# Processor.net
KiCad netlist of a schematic drawn in Altium Designer
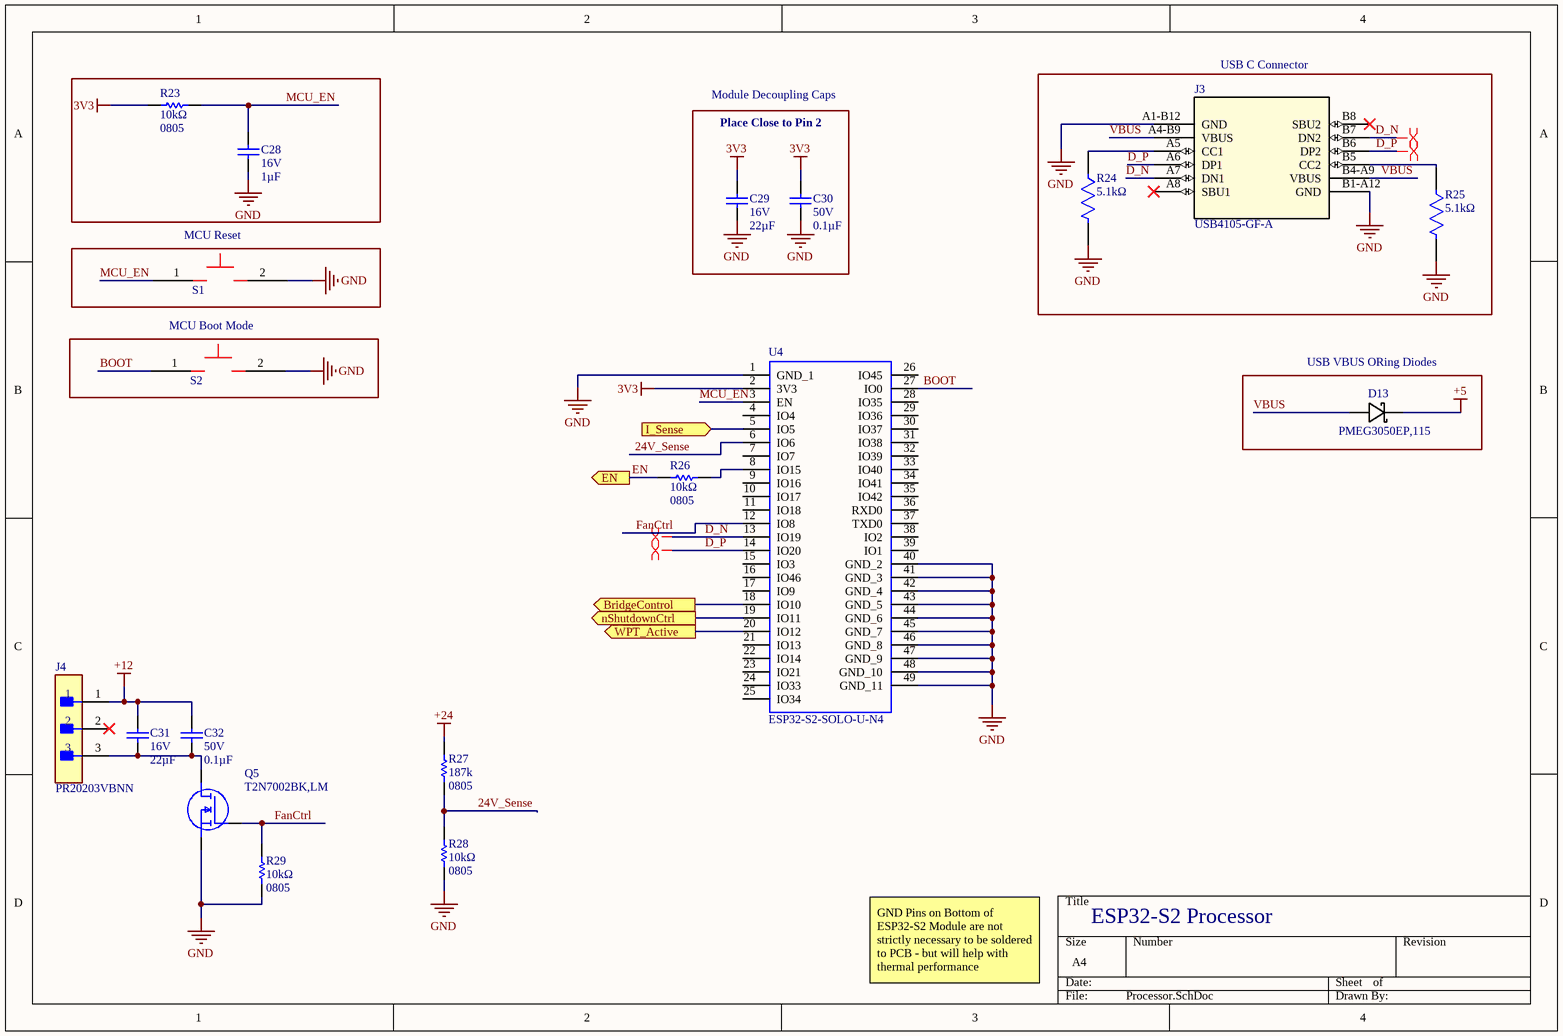
[diagram p0: Processor.SchDoc]

(export (version "E")
  (design (tool "Eeschema 10.0.6"))
  (components
    (comp (ref "C28")
      (value "GRM21BR71C105KA01L")
      (footprint "CAP0805")
      (description "CAP CER 1UF 16V X7R 0805")
      (fields
        (field (name "MANUFACTURER") "Murata Electronics North America")
        (field (name "TOLERANCE") "±10%")
        (field (name "VOLTAGE - RATED") "16V")
        (field (name "CAPACITANCE") "1µF")
      )
      (libsource (lib "Capacitors") (part "GRM21BR71C105KA01L"))
    )
    (comp (ref "C29")
      (value "CL21A226MOCLRNC")
      (footprint "CAP0805")
      (description "CAP CER 22UF 16V X5R 0805")
      (fields
        (field (name "TOLERANCE") "±20%")
        (field (name "VOLTAGE - RATED") "16V")
        (field (name "CAPACITANCE") "22µF")
      )
      (libsource (lib "Capacitors") (part "CL21A226MOCLRNC"))
    )
    (comp (ref "C30")
      (value "C0805C104K5RACTU")
      (footprint "CAP0805")
      (description "CAP CER 0.1UF 50V X7R 0805")
      (fields
        (field (name "TOLERANCE") "±10%")
        (field (name "VOLTAGE - RATED") "50V")
        (field (name "CAPACITANCE") "0.1µF")
      )
      (libsource (lib "Capacitors") (part "C0805C104K5RACTU"))
    )
    (comp (ref "C31")
      (value "CL21A226MOCLRNC")
      (footprint "CAP0805")
      (description "CAP CER 22UF 16V X5R 0805")
      (fields
        (field (name "TOLERANCE") "±20%")
        (field (name "VOLTAGE - RATED") "16V")
        (field (name "CAPACITANCE") "22µF")
      )
      (libsource (lib "Capacitors") (part "CL21A226MOCLRNC"))
    )
    (comp (ref "C32")
      (value "C0805C104K5RACTU")
      (footprint "CAP0805")
      (description "CAP CER 0.1UF 50V X7R 0805")
      (fields
        (field (name "TOLERANCE") "±10%")
        (field (name "VOLTAGE - RATED") "50V")
        (field (name "CAPACITANCE") "0.1µF")
      )
      (libsource (lib "Capacitors") (part "C0805C104K5RACTU"))
    )
    (comp (ref "D13")
      (value "D_PMEG3050EP,115")
      (footprint "SOD-128")
      (description "DIODE SCHOTTKY 360mV 30V 5A")
      (fields (field (name "MFG") "Nexperia") (field (name "MFG_PN") "PMEG3050EP,115"))
      (libsource (lib "Diodes") (part "D_PMEG3050EP,115"))
    )
    (comp (ref "J3")
      (value "USB4105-GF-A")
      (footprint "USB4105_GCT")
      (description "No Description Available")
      (fields (field (name "COPYRIGHT") "Copyright (C) 2022 Ultra Librarian. All rights reserved."))
      (libsource (lib "Connectors and Headers") (part "USB4105-GF-A"))
    )
    (comp (ref "J4")
      (value "PR20203VBNN")
      (footprint "FP-PR20203VBNN-MFG")
      (description "CONN HEADER VERT 3POS 2.54MM")
      (fields
        (field (name "OCTOPART") "https://octopart.com/pr20203vbnn-metz+connect-87667116")
        (field (name "MANUFACTURER") "Metz Connect")
      )
      (libsource (lib "Altium Content Vault") (part "0d3f023dd272f625e17a2be33dea85f"))
    )
    (comp (ref "Q5")
      (value "T2N7002BK,LM")
      (footprint "SamacSys:TBAT54CLM")
      (description "MOSFET (N-Channel)")
      (fields (field (name "MOUSER PART NUMBER") "757-T2N7002BKLM"))
      (libsource (lib "*") (part "T2N7002BK,LM"))
    )
    (comp (ref "R23")
      (value "RC0805FR-0710KL")
      (footprint "RES0805")
      (description "RES SMD 10K OHM 1% 1/8W 0805")
      (fields
        (field (name "MANUFACTURER") "Yageo")
        (field (name "TOLERANCE") "±1%")
        (field (name "RESISTANCE") "10kΩ")
        (field (name "PACKAGE / CASE") "0805")
      )
      (libsource (lib "Resistors") (part "RC0805FR-0710KL"))
    )
    (comp (ref "R24")
      (value "CRCW08055K10FKEA")
      (footprint "FP-CRCW0805-e3-MFG")
      (description "RES Thick Film, 5.1kΩ, 1%, 0.125W, 100ppm/°C, 0805")
      (fields (field (name "TOLERANCE") "1%") (field (name "RESISTANCE") "5.1kΩ"))
      (libsource (lib "Altium Content Vault") (part "1029c3af85768c4190bb7ad29bc67b5"))
    )
    (comp (ref "R25")
      (value "CRCW08055K10FKEA")
      (footprint "FP-CRCW0805-e3-MFG")
      (description "RES Thick Film, 5.1kΩ, 1%, 0.125W, 100ppm/°C, 0805")
      (fields (field (name "TOLERANCE") "1%") (field (name "RESISTANCE") "5.1kΩ"))
      (libsource (lib "Altium Content Vault") (part "1029c3af85768c4190bb7ad29bc67b5"))
    )
    (comp (ref "R26")
      (value "RC0805FR-0710KL")
      (footprint "RES0805")
      (description "RES SMD 10K OHM 1% 1/8W 0805")
      (fields
        (field (name "MANUFACTURER") "Yageo")
        (field (name "TOLERANCE") "±1%")
        (field (name "RESISTANCE") "10kΩ")
        (field (name "PACKAGE / CASE") "0805")
      )
      (libsource (lib "Resistors") (part "RC0805FR-0710KL"))
    )
    (comp (ref "R27")
      (value "ERJ-6ENF1873V")
      (footprint "RESC2013X70X40NL20T20")
      (fields
        (field (name "MANUFACTURER") "Panasonic")
        (field (name "RESISTANCE") "187k")
        (field (name "PACKAGE") "0805")
      )
      (libsource (lib "Altium Content Vault") (part "RES"))
    )
    (comp (ref "R28")
      (value "RC0805FR-0710KL")
      (footprint "RES0805")
      (description "RES SMD 10K OHM 1% 1/8W 0805")
      (fields
        (field (name "MANUFACTURER") "Yageo")
        (field (name "TOLERANCE") "±1%")
        (field (name "RESISTANCE") "10kΩ")
        (field (name "PACKAGE / CASE") "0805")
      )
      (libsource (lib "Resistors") (part "RC0805FR-0710KL"))
    )
    (comp (ref "R29")
      (value "RC0805FR-0710KL")
      (footprint "RES0805")
      (description "RES SMD 10K OHM 1% 1/8W 0805")
      (fields
        (field (name "MANUFACTURER") "Yageo")
        (field (name "TOLERANCE") "±1%")
        (field (name "RESISTANCE") "10kΩ")
        (field (name "PACKAGE / CASE") "0805")
      )
      (libsource (lib "Resistors") (part "RC0805FR-0710KL"))
    )
    (comp (ref "S1")
      (value "RESET")
      (footprint "Tactile_Button_3X6X2")
      (description "Tactile Button_3X6X2")
      (libsource (lib "Mechanical_Devices") (part "Tactile Button_3X6X2"))
    )
    (comp (ref "S2")
      (value "BOOT")
      (footprint "Tactile_Button_3X6X2")
      (description "Tactile Button_3X6X2")
      (libsource (lib "Mechanical_Devices") (part "Tactile Button_3X6X2"))
    )
    (comp (ref "U4")
      (value "ESP32-S2-SOLO-U-N4")
      (footprint "ESP32S2SOLOUN4")
      (description "WiFi Modules - 802.11 SMD module, ESP32-S2, 4 MB SPI flash, IPEX antenna")
      (fields (field (name "MOUSER PART NUMBER") "356-ESP32-S2-SOLOUN4"))
      (libsource (lib "Microcontrollers") (part "ESP32-S2-SOLO-U-N4"))
    )
  )
  (nets
    (net (code "1") (name "+5") (class "Default") (node (ref "D13") (pin "2") (pintype "passive")))
    (net (code "2") (name "+12") (class "Default")
      (node (ref "C31") (pin "2") (pinfunction "2_2") (pintype "passive"))
      (node (ref "C32") (pin "2") (pinfunction "2_2") (pintype "passive"))
      (node (ref "J4") (pin "1") (pinfunction "1_1") (pintype "passive"))
    )
    (net (code "3") (name "+24") (class "Default")
      (node (ref "R27") (pin "1") (pinfunction "1_1") (pintype "passive"))
    )
    (net (code "4") (name "/24V_Sense") (class "Default")
      (node (ref "R27") (pin "2") (pinfunction "2_2") (pintype "passive"))
      (node (ref "R28") (pin "2") (pinfunction "2_2") (pintype "passive"))
      (node (ref "U4") (pin "6") (pinfunction "IO6_6") (pintype "passive"))
    )
    (net (code "5") (name "/BOOT") (class "Default")
      (node (ref "S2") (pin "1") (pinfunction "1_1") (pintype "passive"))
      (node (ref "U4") (pin "27") (pinfunction "IO0_27") (pintype "passive"))
    )
    (net (code "6") (name "/BridgeControl") (class "Default")
      (node (ref "U4") (pin "18") (pinfunction "IO10_18") (pintype "passive"))
    )
    (net (code "7") (name "/D_N") (class "Default")
      (node (ref "J3") (pin "A7") (pinfunction "DN1_A7") (pintype "bidirectional"))
      (node (ref "J3") (pin "B7") (pinfunction "DN2_B7") (pintype "bidirectional"))
      (node (ref "U4") (pin "13") (pinfunction "IO19_13") (pintype "passive"))
    )
    (net (code "8") (name "/D_P") (class "Default")
      (node (ref "J3") (pin "A6") (pinfunction "DP1_A6") (pintype "bidirectional"))
      (node (ref "J3") (pin "B6") (pinfunction "DP2_B6") (pintype "bidirectional"))
      (node (ref "U4") (pin "14") (pinfunction "IO20_14") (pintype "passive"))
    )
    (net (code "9") (name "/EN") (class "Default")
      (node (ref "R26") (pin "1") (pinfunction "1_1") (pintype "passive"))
    )
    (net (code "10") (name "/FanCtrl") (class "Default")
      (node (ref "Q5") (pin "1") (pinfunction "G_1") (pintype "passive"))
      (node (ref "R29") (pin "2") (pinfunction "2_2") (pintype "passive"))
      (node (ref "U4") (pin "12") (pinfunction "IO8_12") (pintype "passive"))
    )
    (net (code "11") (name "/I_Sense") (class "Default")
      (node (ref "U4") (pin "5") (pinfunction "IO5_5") (pintype "passive"))
    )
    (net (code "12") (name "/MCU_EN") (class "Default")
      (node (ref "C28") (pin "2") (pinfunction "2_2") (pintype "passive"))
      (node (ref "R23") (pin "2") (pinfunction "2_2") (pintype "passive"))
      (node (ref "S1") (pin "1") (pinfunction "1_1") (pintype "passive"))
      (node (ref "U4") (pin "3") (pinfunction "EN_3") (pintype "passive"))
    )
    (net (code "13") (name "/VBUS") (class "Default")
      (node (ref "D13") (pin "1") (pintype "passive"))
      (node (ref "J3") (pin "A4-B9") (pinfunction "VBUS_A4-B9") (pintype "power_in"))
      (node (ref "J3") (pin "B4-A9") (pinfunction "VBUS_B4-A9") (pintype "power_in"))
    )
    (net (code "14") (name "/WPT_Active") (class "Default")
      (node (ref "U4") (pin "20") (pinfunction "IO12_20") (pintype "passive"))
    )
    (net (code "15") (name "/nShutdownCtrl") (class "Default")
      (node (ref "U4") (pin "19") (pinfunction "IO11_19") (pintype "passive"))
    )
    (net (code "16") (name "3V3") (class "Default")
      (node (ref "C29") (pin "2") (pinfunction "2_2") (pintype "passive"))
      (node (ref "C30") (pin "2") (pinfunction "2_2") (pintype "passive"))
      (node (ref "R23") (pin "1") (pinfunction "1_1") (pintype "passive"))
      (node (ref "U4") (pin "2") (pinfunction "3V3_2") (pintype "passive"))
    )
    (net (code "17") (name "GND") (class "Default")
      (node (ref "C28") (pin "1") (pinfunction "1_1") (pintype "passive"))
      (node (ref "C29") (pin "1") (pinfunction "1_1") (pintype "passive"))
      (node (ref "C30") (pin "1") (pinfunction "1_1") (pintype "passive"))
      (node (ref "J3") (pin "A1-B12") (pinfunction "GND_A1-B12") (pintype "passive"))
      (node (ref "J3") (pin "B1-A12") (pinfunction "GND_B1-A12") (pintype "passive"))
      (node (ref "Q5") (pin "2") (pinfunction "S_2") (pintype "passive"))
      (node (ref "R24") (pin "2") (pinfunction "2_2") (pintype "passive"))
      (node (ref "R25") (pin "2") (pinfunction "2_2") (pintype "passive"))
      (node (ref "R28") (pin "1") (pinfunction "1_1") (pintype "passive"))
      (node (ref "R29") (pin "1") (pinfunction "1_1") (pintype "passive"))
      (node (ref "S1") (pin "2") (pinfunction "2_2") (pintype "passive"))
      (node (ref "S2") (pin "2") (pinfunction "2_2") (pintype "passive"))
      (node (ref "U4") (pin "1") (pinfunction "GND_1_1") (pintype "passive"))
      (node (ref "U4") (pin "40") (pinfunction "GND_2_40") (pintype "passive"))
      (node (ref "U4") (pin "41") (pinfunction "GND_3_41") (pintype "passive"))
      (node (ref "U4") (pin "42") (pinfunction "GND_4_42") (pintype "passive"))
      (node (ref "U4") (pin "43") (pinfunction "GND_5_43") (pintype "passive"))
      (node (ref "U4") (pin "44") (pinfunction "GND_6_44") (pintype "passive"))
      (node (ref "U4") (pin "45") (pinfunction "GND_7_45") (pintype "passive"))
      (node (ref "U4") (pin "46") (pinfunction "GND_8_46") (pintype "passive"))
      (node (ref "U4") (pin "47") (pinfunction "GND_9_47") (pintype "passive"))
      (node (ref "U4") (pin "48") (pinfunction "GND_10_48") (pintype "passive"))
      (node (ref "U4") (pin "49") (pinfunction "GND_11_49") (pintype "passive"))
    )
    (net (code "18") (name "Net-(J3-CC1)") (class "Default")
      (node (ref "J3") (pin "A5") (pinfunction "CC1_A5") (pintype "bidirectional"))
      (node (ref "R24") (pin "1") (pinfunction "1_1") (pintype "passive"))
    )
    (net (code "19") (name "Net-(J3-CC2)") (class "Default")
      (node (ref "J3") (pin "B5") (pinfunction "CC2_B5") (pintype "bidirectional"))
      (node (ref "R25") (pin "1") (pinfunction "1_1") (pintype "passive"))
    )
    (net (code "20") (name "Net-(Q5-D)") (class "Default")
      (node (ref "C31") (pin "1") (pinfunction "1_1") (pintype "passive"))
      (node (ref "C32") (pin "1") (pinfunction "1_1") (pintype "passive"))
      (node (ref "J4") (pin "3") (pinfunction "3_3") (pintype "passive"))
      (node (ref "Q5") (pin "3") (pinfunction "D_3") (pintype "passive"))
    )
    (net (code "21") (name "Net-(U4-IO15)") (class "Default")
      (node (ref "R26") (pin "2") (pinfunction "2_2") (pintype "passive"))
      (node (ref "U4") (pin "8") (pinfunction "IO15_8") (pintype "passive"))
    )
    (net (code "22") (name "unconnected-(J3-SBU1-PadA8)") (class "Default")
      (node (ref "J3") (pin "A8") (pinfunction "SBU1_A8") (pintype "bidirectional+no_connect"))
    )
    (net (code "23") (name "unconnected-(J3-SBU2-PadB8)") (class "Default")
      (node (ref "J3") (pin "B8") (pinfunction "SBU2_B8") (pintype "bidirectional+no_connect"))
    )
    (net (code "24") (name "unconnected-(J4-Pad2)") (class "Default")
      (node (ref "J4") (pin "2") (pinfunction "2_2") (pintype "passive+no_connect"))
    )
    (net (code "25") (name "unconnected-(U4-IO1-Pad39)") (class "Default")
      (node (ref "U4") (pin "39") (pinfunction "IO1_39") (pintype "passive"))
    )
    (net (code "26") (name "unconnected-(U4-IO2-Pad38)") (class "Default")
      (node (ref "U4") (pin "38") (pinfunction "IO2_38") (pintype "passive"))
    )
    (net (code "27") (name "unconnected-(U4-IO3-Pad15)") (class "Default")
      (node (ref "U4") (pin "15") (pinfunction "IO3_15") (pintype "passive"))
    )
    (net (code "28") (name "unconnected-(U4-IO4-Pad4)") (class "Default")
      (node (ref "U4") (pin "4") (pinfunction "IO4_4") (pintype "passive"))
    )
    (net (code "29") (name "unconnected-(U4-IO7-Pad7)") (class "Default")
      (node (ref "U4") (pin "7") (pinfunction "IO7_7") (pintype "passive"))
    )
    (net (code "30") (name "unconnected-(U4-IO9-Pad17)") (class "Default")
      (node (ref "U4") (pin "17") (pinfunction "IO9_17") (pintype "passive"))
    )
    (net (code "31") (name "unconnected-(U4-IO13-Pad21)") (class "Default")
      (node (ref "U4") (pin "21") (pinfunction "IO13_21") (pintype "passive"))
    )
    (net (code "32") (name "unconnected-(U4-IO14-Pad22)") (class "Default")
      (node (ref "U4") (pin "22") (pinfunction "IO14_22") (pintype "passive"))
    )
    (net (code "33") (name "unconnected-(U4-IO16-Pad9)") (class "Default")
      (node (ref "U4") (pin "9") (pinfunction "IO16_9") (pintype "passive"))
    )
    (net (code "34") (name "unconnected-(U4-IO17-Pad10)") (class "Default")
      (node (ref "U4") (pin "10") (pinfunction "IO17_10") (pintype "passive"))
    )
    (net (code "35") (name "unconnected-(U4-IO18-Pad11)") (class "Default")
      (node (ref "U4") (pin "11") (pinfunction "IO18_11") (pintype "passive"))
    )
    (net (code "36") (name "unconnected-(U4-IO21-Pad23)") (class "Default")
      (node (ref "U4") (pin "23") (pinfunction "IO21_23") (pintype "passive"))
    )
    (net (code "37") (name "unconnected-(U4-IO33-Pad24)") (class "Default")
      (node (ref "U4") (pin "24") (pinfunction "IO33_24") (pintype "passive"))
    )
    (net (code "38") (name "unconnected-(U4-IO34-Pad25)") (class "Default")
      (node (ref "U4") (pin "25") (pinfunction "IO34_25") (pintype "passive"))
    )
    (net (code "39") (name "unconnected-(U4-IO35-Pad28)") (class "Default")
      (node (ref "U4") (pin "28") (pinfunction "IO35_28") (pintype "passive"))
    )
    (net (code "40") (name "unconnected-(U4-IO36-Pad29)") (class "Default")
      (node (ref "U4") (pin "29") (pinfunction "IO36_29") (pintype "passive"))
    )
    (net (code "41") (name "unconnected-(U4-IO37-Pad30)") (class "Default")
      (node (ref "U4") (pin "30") (pinfunction "IO37_30") (pintype "passive"))
    )
    (net (code "42") (name "unconnected-(U4-IO38-Pad31)") (class "Default")
      (node (ref "U4") (pin "31") (pinfunction "IO38_31") (pintype "passive"))
    )
    (net (code "43") (name "unconnected-(U4-IO39-Pad32)") (class "Default")
      (node (ref "U4") (pin "32") (pinfunction "IO39_32") (pintype "passive"))
    )
    (net (code "44") (name "unconnected-(U4-IO40-Pad33)") (class "Default")
      (node (ref "U4") (pin "33") (pinfunction "IO40_33") (pintype "passive"))
    )
    (net (code "45") (name "unconnected-(U4-IO41-Pad34)") (class "Default")
      (node (ref "U4") (pin "34") (pinfunction "IO41_34") (pintype "passive"))
    )
    (net (code "46") (name "unconnected-(U4-IO42-Pad35)") (class "Default")
      (node (ref "U4") (pin "35") (pinfunction "IO42_35") (pintype "passive"))
    )
    (net (code "47") (name "unconnected-(U4-IO45-Pad26)") (class "Default")
      (node (ref "U4") (pin "26") (pinfunction "IO45_26") (pintype "passive"))
    )
    (net (code "48") (name "unconnected-(U4-IO46-Pad16)") (class "Default")
      (node (ref "U4") (pin "16") (pinfunction "IO46_16") (pintype "passive"))
    )
    (net (code "49") (name "unconnected-(U4-RXD0-Pad36)") (class "Default")
      (node (ref "U4") (pin "36") (pinfunction "RXD0_36") (pintype "passive"))
    )
    (net (code "50") (name "unconnected-(U4-TXD0-Pad37)") (class "Default")
      (node (ref "U4") (pin "37") (pinfunction "TXD0_37") (pintype "passive"))
    )
  )
)
